# prod5.net
KiCad netlist of a schematic drawn in EAGLE
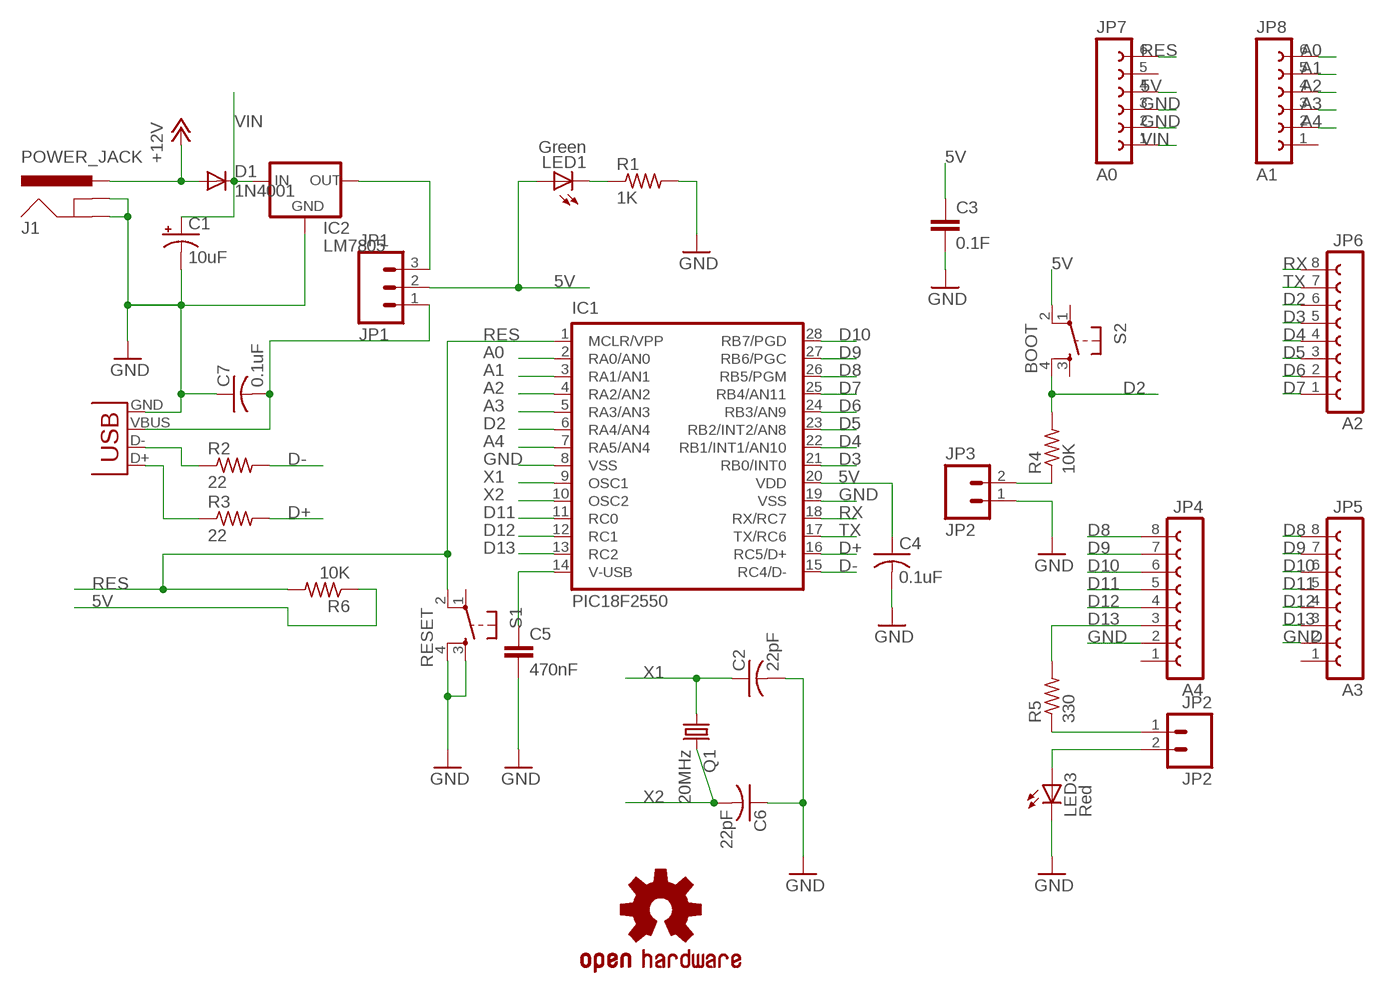
[diagram p0: schematic, sheet 1]

(export (version "E")
  (design (tool "Eeschema 10.0.6"))
  (components
    (comp (ref "C1")
      (value "10uF")
      (footprint "eagle-import:CPOL-RADIAL-10UF-25V")
      (libsource (lib "eagle-import") (part "CAP_POLPTH2"))
    )
    (comp (ref "C2")
      (value "22pF")
      (footprint "eagle-import:C025-025X050")
      (libsource (lib "eagle-import") (part "C-US025-025X050"))
    )
    (comp (ref "C3")
      (value "0.1F")
      (footprint "eagle-import:CAP-PTH-5MM")
      (libsource (lib "eagle-import") (part "CAPPTH1"))
    )
    (comp (ref "C4")
      (value "0.1uF")
      (footprint "eagle-import:C025-025X050")
      (libsource (lib "eagle-import") (part "C-US025-025X050"))
    )
    (comp (ref "C5")
      (value "470nF")
      (footprint "eagle-import:CAP-PTH-5MM")
      (libsource (lib "eagle-import") (part "CAPPTH1"))
    )
    (comp (ref "C6")
      (value "22pF")
      (footprint "eagle-import:C025-025X050")
      (libsource (lib "eagle-import") (part "C-US025-025X050"))
    )
    (comp (ref "C7")
      (value "0.1uF")
      (footprint "eagle-import:C025-025X050")
      (libsource (lib "eagle-import") (part "C-US025-025X050"))
    )
    (comp (ref "D1")
      (value "1N4001")
      (footprint "eagle-import:DIODE-1N4001")
      (libsource (lib "eagle-import") (part "DIODEPTH"))
    )
    (comp (ref "IC1")
      (value "PIC18F2550")
      (footprint "eagle-import:DIL28-3")
      (libsource (lib "eagle-import") (part "PIC18F2550"))
    )
    (comp (ref "IC2")
      (value "LM7805")
      (footprint "eagle-import:78XXL")
      (libsource (lib "eagle-import") (part "V_REG_78XXSIDE"))
    )
    (comp (ref "J1")
      (value "POWER_JACK")
      (footprint "eagle-import:POWER_JACK_PTH")
      (libsource (lib "eagle-import") (part "POWER_JACKPTH"))
    )
    (comp (ref "JP1")
      (value "JP1")
      (footprint "eagle-import:1X03")
      (libsource (lib "eagle-import") (part "M03PTH"))
    )
    (comp (ref "JP2")
      (value "JP2")
      (footprint "eagle-import:1X02")
      (libsource (lib "eagle-import") (part "M02PTH"))
    )
    (comp (ref "JP3")
      (value "JP2")
      (footprint "eagle-import:1X02")
      (libsource (lib "eagle-import") (part "M02PTH"))
    )
    (comp (ref "JP4")
      (value "A4")
      (footprint "eagle-import:FE08")
      (libsource (lib "eagle-import") (part "FE08-1"))
    )
    (comp (ref "JP5")
      (value "A3")
      (footprint "eagle-import:FE08")
      (libsource (lib "eagle-import") (part "FE08-1"))
    )
    (comp (ref "JP6")
      (value "A2")
      (footprint "eagle-import:FE08")
      (libsource (lib "eagle-import") (part "FE08-1"))
    )
    (comp (ref "JP7")
      (value "A0")
      (footprint "eagle-import:FE06")
      (libsource (lib "eagle-import") (part "FE06-1"))
    )
    (comp (ref "JP8")
      (value "A1")
      (footprint "eagle-import:FE06")
      (libsource (lib "eagle-import") (part "FE06-1"))
    )
    (comp (ref "LED1")
      (value "Green")
      (footprint "eagle-import:LED3MM")
      (libsource (lib "eagle-import") (part "LED3MM"))
    )
    (comp (ref "LED3")
      (value "Red")
      (footprint "eagle-import:LED3MM")
      (libsource (lib "eagle-import") (part "LED3MM"))
    )
    (comp (ref "LOGO1")
      (value "OSHW-LOGOM")
      (footprint "eagle-import:OSHW-LOGO-M")
      (libsource (lib "eagle-import") (part "OSHW-LOGOM"))
    )
    (comp (ref "Q1")
      (value "20MHz")
      (footprint "eagle-import:HC49_S")
      (libsource (lib "eagle-import") (part "CRYSTALHC49S"))
    )
    (comp (ref "R1")
      (value "1K")
      (footprint "eagle-import:0204_7")
      (libsource (lib "eagle-import") (part "R-US_0204/7"))
    )
    (comp (ref "R2")
      (value "22")
      (footprint "eagle-import:0207_15")
      (libsource (lib "eagle-import") (part "R-US_0207/15"))
    )
    (comp (ref "R3")
      (value "22")
      (footprint "eagle-import:0207_15")
      (libsource (lib "eagle-import") (part "R-US_0207/15"))
    )
    (comp (ref "R4")
      (value "10K")
      (footprint "eagle-import:0207_15")
      (libsource (lib "eagle-import") (part "R-US_0207/15"))
    )
    (comp (ref "R5")
      (value "330")
      (footprint "eagle-import:0204_7")
      (libsource (lib "eagle-import") (part "R-US_0204/7"))
    )
    (comp (ref "R6")
      (value "10K")
      (footprint "eagle-import:0204_7")
      (libsource (lib "eagle-import") (part "R-US_0204/7"))
    )
    (comp (ref "S1")
      (value "RESET")
      (footprint "eagle-import:TACTILE-PTH")
      (libsource (lib "eagle-import") (part "TAC_SWITCHPTH"))
    )
    (comp (ref "S2")
      (value "BOOT")
      (footprint "eagle-import:TACTILE-PTH")
      (libsource (lib "eagle-import") (part "TAC_SWITCHPTH"))
    )
    (comp (ref "X1")
      (value "USBPTH")
      (footprint "eagle-import:USB-B-PTH")
      (libsource (lib "eagle-import") (part "USBPTH"))
    )
  )
  (nets
    (net (code "1") (name "+12V") (class "Default")
      (node (ref "D1") (pin "A") (pinfunction "A_A") (pintype "passive"))
      (node (ref "J1") (pin "PWR") (pinfunction "PWR_PWR") (pintype "bidirectional"))
    )
    (net (code "2") (name "/5V") (class "Default")
      (node (ref "C3") (pin "1") (pinfunction "1_1") (pintype "passive"))
      (node (ref "C4") (pin "1") (pinfunction "1_1") (pintype "passive"))
      (node (ref "IC1") (pin "20") (pinfunction "VDD_20") (pintype "power_in"))
      (node (ref "JP1") (pin "2") (pinfunction "2_2") (pintype "passive"))
      (node (ref "JP7") (pin "4") (pinfunction "4_4") (pintype "passive"))
      (node (ref "LED1") (pin "A") (pinfunction "A_A") (pintype "passive"))
      (node (ref "R6") (pin "1") (pinfunction "1_1") (pintype "passive"))
      (node (ref "S2") (pin "2") (pinfunction "2_2") (pintype "passive"))
    )
    (net (code "3") (name "/A0") (class "Default")
      (node (ref "IC1") (pin "2") (pinfunction "RA0/AN0_2") (pintype "bidirectional"))
      (node (ref "JP8") (pin "6") (pinfunction "6_6") (pintype "passive"))
    )
    (net (code "4") (name "/A1") (class "Default")
      (node (ref "IC1") (pin "3") (pinfunction "RA1/AN1_3") (pintype "bidirectional"))
      (node (ref "JP8") (pin "5") (pinfunction "5_5") (pintype "passive"))
    )
    (net (code "5") (name "/A2") (class "Default")
      (node (ref "IC1") (pin "4") (pinfunction "RA2/AN2_4") (pintype "bidirectional"))
      (node (ref "JP8") (pin "4") (pinfunction "4_4") (pintype "passive"))
    )
    (net (code "6") (name "/A3") (class "Default")
      (node (ref "IC1") (pin "5") (pinfunction "RA3/AN3_5") (pintype "bidirectional"))
      (node (ref "JP8") (pin "3") (pinfunction "3_3") (pintype "passive"))
    )
    (net (code "7") (name "/A4") (class "Default")
      (node (ref "IC1") (pin "7") (pinfunction "RA5/AN4_7") (pintype "bidirectional"))
      (node (ref "JP8") (pin "2") (pinfunction "2_2") (pintype "passive"))
    )
    (net (code "8") (name "/D+") (class "Default")
      (node (ref "IC1") (pin "16") (pinfunction "RC5/D+_16") (pintype "bidirectional"))
      (node (ref "R3") (pin "2") (pinfunction "2_2") (pintype "passive"))
    )
    (net (code "9") (name "/D-") (class "Default")
      (node (ref "IC1") (pin "15") (pinfunction "RC4/D-_15") (pintype "bidirectional"))
      (node (ref "R2") (pin "2") (pinfunction "2_2") (pintype "passive"))
    )
    (net (code "10") (name "/D2") (class "Default")
      (node (ref "IC1") (pin "6") (pinfunction "RA4/AN4_6") (pintype "bidirectional"))
      (node (ref "JP6") (pin "6") (pinfunction "6_6") (pintype "passive"))
      (node (ref "R4") (pin "2") (pinfunction "2_2") (pintype "passive"))
      (node (ref "S2") (pin "4") (pinfunction "4_4") (pintype "passive"))
    )
    (net (code "11") (name "/D3") (class "Default")
      (node (ref "IC1") (pin "21") (pinfunction "RB0/INT0_21") (pintype "bidirectional"))
      (node (ref "JP6") (pin "5") (pinfunction "5_5") (pintype "passive"))
    )
    (net (code "12") (name "/D4") (class "Default")
      (node (ref "IC1") (pin "22") (pinfunction "RB1/INT1/AN10_22") (pintype "bidirectional"))
      (node (ref "JP6") (pin "4") (pinfunction "4_4") (pintype "passive"))
    )
    (net (code "13") (name "/D5") (class "Default")
      (node (ref "IC1") (pin "23") (pinfunction "RB2/INT2/AN8_23") (pintype "bidirectional"))
      (node (ref "JP6") (pin "3") (pinfunction "3_3") (pintype "passive"))
    )
    (net (code "14") (name "/D6") (class "Default")
      (node (ref "IC1") (pin "24") (pinfunction "RB3/AN9_24") (pintype "bidirectional"))
      (node (ref "JP6") (pin "2") (pinfunction "2_2") (pintype "passive"))
    )
    (net (code "15") (name "/D7") (class "Default")
      (node (ref "IC1") (pin "25") (pinfunction "RB4/AN11_25") (pintype "bidirectional"))
      (node (ref "JP6") (pin "1") (pinfunction "1_1") (pintype "passive"))
    )
    (net (code "16") (name "/D8") (class "Default")
      (node (ref "IC1") (pin "26") (pinfunction "RB5/PGM_26") (pintype "bidirectional"))
      (node (ref "JP4") (pin "8") (pinfunction "8_8") (pintype "passive"))
      (node (ref "JP5") (pin "8") (pinfunction "8_8") (pintype "passive"))
    )
    (net (code "17") (name "/D9") (class "Default")
      (node (ref "IC1") (pin "27") (pinfunction "RB6/PGC_27") (pintype "bidirectional"))
      (node (ref "JP4") (pin "7") (pinfunction "7_7") (pintype "passive"))
      (node (ref "JP5") (pin "7") (pinfunction "7_7") (pintype "passive"))
    )
    (net (code "18") (name "/D10") (class "Default")
      (node (ref "IC1") (pin "28") (pinfunction "RB7/PGD_28") (pintype "bidirectional"))
      (node (ref "JP4") (pin "6") (pinfunction "6_6") (pintype "passive"))
      (node (ref "JP5") (pin "6") (pinfunction "6_6") (pintype "passive"))
    )
    (net (code "19") (name "/D11") (class "Default")
      (node (ref "IC1") (pin "11") (pinfunction "RC0_11") (pintype "bidirectional"))
      (node (ref "JP4") (pin "5") (pinfunction "5_5") (pintype "passive"))
      (node (ref "JP5") (pin "5") (pinfunction "5_5") (pintype "passive"))
    )
    (net (code "20") (name "/D12") (class "Default")
      (node (ref "IC1") (pin "12") (pinfunction "RC1_12") (pintype "bidirectional"))
      (node (ref "JP4") (pin "4") (pinfunction "4_4") (pintype "passive"))
      (node (ref "JP5") (pin "4") (pinfunction "4_4") (pintype "passive"))
    )
    (net (code "21") (name "/D13") (class "Default")
      (node (ref "IC1") (pin "13") (pinfunction "RC2_13") (pintype "bidirectional"))
      (node (ref "JP4") (pin "3") (pinfunction "3_3") (pintype "passive"))
      (node (ref "JP5") (pin "3") (pinfunction "3_3") (pintype "passive"))
      (node (ref "R5") (pin "2") (pinfunction "2_2") (pintype "passive"))
    )
    (net (code "22") (name "/RES") (class "Default")
      (node (ref "IC1") (pin "1") (pinfunction "MCLR/VPP_1") (pintype "bidirectional"))
      (node (ref "JP7") (pin "6") (pinfunction "6_6") (pintype "passive"))
      (node (ref "R6") (pin "2") (pinfunction "2_2") (pintype "passive"))
      (node (ref "S1") (pin "2") (pinfunction "2_2") (pintype "passive"))
    )
    (net (code "23") (name "/RX") (class "Default")
      (node (ref "IC1") (pin "18") (pinfunction "RX/RC7_18") (pintype "input"))
      (node (ref "JP6") (pin "8") (pinfunction "8_8") (pintype "passive"))
    )
    (net (code "24") (name "/TX") (class "Default")
      (node (ref "IC1") (pin "17") (pinfunction "TX/RC6_17") (pintype "bidirectional"))
      (node (ref "JP6") (pin "7") (pinfunction "7_7") (pintype "passive"))
    )
    (net (code "25") (name "/VIN") (class "Default")
      (node (ref "C1") (pin "1") (pinfunction "+_1") (pintype "passive"))
      (node (ref "D1") (pin "C") (pinfunction "C_C") (pintype "passive"))
      (node (ref "IC2") (pin "IN") (pinfunction "IN_IN") (pintype "input"))
      (node (ref "JP7") (pin "1") (pinfunction "1_1") (pintype "passive"))
    )
    (net (code "26") (name "/X1") (class "Default")
      (node (ref "C2") (pin "1") (pinfunction "1_1") (pintype "passive"))
      (node (ref "IC1") (pin "9") (pinfunction "OSC1_9") (pintype "bidirectional"))
      (node (ref "Q1") (pin "1") (pinfunction "1_1") (pintype "passive"))
    )
    (net (code "27") (name "/X2") (class "Default")
      (node (ref "C6") (pin "2") (pinfunction "2_2") (pintype "passive"))
      (node (ref "IC1") (pin "10") (pinfunction "OSC2_10") (pintype "bidirectional"))
      (node (ref "Q1") (pin "2") (pinfunction "2_2") (pintype "passive"))
    )
    (net (code "28") (name "GND") (class "Default")
      (node (ref "C1") (pin "2") (pinfunction "-_2") (pintype "passive"))
      (node (ref "C2") (pin "2") (pinfunction "2_2") (pintype "passive"))
      (node (ref "C3") (pin "2") (pinfunction "2_2") (pintype "passive"))
      (node (ref "C4") (pin "2") (pinfunction "2_2") (pintype "passive"))
      (node (ref "C5") (pin "2") (pinfunction "2_2") (pintype "passive"))
      (node (ref "C6") (pin "1") (pinfunction "1_1") (pintype "passive"))
      (node (ref "C7") (pin "1") (pinfunction "1_1") (pintype "passive"))
      (node (ref "IC1") (pin "19") (pinfunction "VSS_19") (pintype "power_in"))
      (node (ref "IC1") (pin "8") (pinfunction "VSS_8") (pintype "power_in"))
      (node (ref "IC2") (pin "GND") (pinfunction "GND_GND") (pintype "input"))
      (node (ref "J1") (pin "GND") (pinfunction "GND_GND") (pintype "bidirectional"))
      (node (ref "J1") (pin "GNDBREAK") (pinfunction "GNDBREAK_GNDBREAK") (pintype "bidirectional"))
      (node (ref "JP3") (pin "1") (pinfunction "1_1") (pintype "passive"))
      (node (ref "JP4") (pin "2") (pinfunction "2_2") (pintype "passive"))
      (node (ref "JP5") (pin "2") (pinfunction "2_2") (pintype "passive"))
      (node (ref "JP7") (pin "2") (pinfunction "2_2") (pintype "passive"))
      (node (ref "JP7") (pin "3") (pinfunction "3_3") (pintype "passive"))
      (node (ref "LED3") (pin "K") (pinfunction "C_K") (pintype "passive"))
      (node (ref "R1") (pin "2") (pinfunction "2_2") (pintype "passive"))
      (node (ref "S1") (pin "3") (pinfunction "3_3") (pintype "passive"))
      (node (ref "S1") (pin "4") (pinfunction "4_4") (pintype "passive"))
      (node (ref "X1") (pin "GND") (pinfunction "GND_GND") (pintype "bidirectional"))
    )
    (net (code "29") (name "Net-(C7-Pad2)") (class "Default")
      (node (ref "C7") (pin "2") (pinfunction "2_2") (pintype "passive"))
      (node (ref "JP1") (pin "1") (pinfunction "1_1") (pintype "passive"))
      (node (ref "X1") (pin "VBUS") (pinfunction "VBUS_VBUS") (pintype "bidirectional"))
    )
    (net (code "30") (name "Net-(IC1-V-USB)") (class "Default")
      (node (ref "C5") (pin "1") (pinfunction "1_1") (pintype "passive"))
      (node (ref "IC1") (pin "14") (pinfunction "V-USB_14") (pintype "bidirectional"))
    )
    (net (code "31") (name "Net-(IC2-PadOUT)") (class "Default")
      (node (ref "IC2") (pin "OUT") (pinfunction "OUT_OUT") (pintype "output"))
      (node (ref "JP1") (pin "3") (pinfunction "3_3") (pintype "passive"))
    )
    (net (code "32") (name "Net-(JP2-Pad1)") (class "Default")
      (node (ref "JP2") (pin "1") (pinfunction "1_1") (pintype "passive"))
      (node (ref "R5") (pin "1") (pinfunction "1_1") (pintype "passive"))
    )
    (net (code "33") (name "Net-(JP2-Pad2)") (class "Default")
      (node (ref "JP2") (pin "2") (pinfunction "2_2") (pintype "passive"))
      (node (ref "LED3") (pin "A") (pinfunction "A_A") (pintype "passive"))
    )
    (net (code "34") (name "Net-(JP3-Pad2)") (class "Default")
      (node (ref "JP3") (pin "2") (pinfunction "2_2") (pintype "passive"))
      (node (ref "R4") (pin "1") (pinfunction "1_1") (pintype "passive"))
    )
    (net (code "35") (name "Net-(LED1-C)") (class "Default")
      (node (ref "LED1") (pin "K") (pinfunction "C_K") (pintype "passive"))
      (node (ref "R1") (pin "1") (pinfunction "1_1") (pintype "passive"))
    )
    (net (code "36") (name "Net-(R2-Pad1)") (class "Default")
      (node (ref "R2") (pin "1") (pinfunction "1_1") (pintype "passive"))
      (node (ref "X1") (pin "D-") (pinfunction "D-_D-") (pintype "bidirectional"))
    )
    (net (code "37") (name "Net-(R3-Pad1)") (class "Default")
      (node (ref "R3") (pin "1") (pinfunction "1_1") (pintype "passive"))
      (node (ref "X1") (pin "D+") (pinfunction "D+_D+") (pintype "bidirectional"))
    )
    (net (code "38") (name "unconnected-(JP4-Pad1)") (class "Default")
      (node (ref "JP4") (pin "1") (pinfunction "1_1") (pintype "passive"))
    )
    (net (code "39") (name "unconnected-(JP5-Pad1)") (class "Default")
      (node (ref "JP5") (pin "1") (pinfunction "1_1") (pintype "passive"))
    )
    (net (code "40") (name "unconnected-(JP7-Pad5)") (class "Default")
      (node (ref "JP7") (pin "5") (pinfunction "5_5") (pintype "passive"))
    )
    (net (code "41") (name "unconnected-(JP8-Pad1)") (class "Default")
      (node (ref "JP8") (pin "1") (pinfunction "1_1") (pintype "passive"))
    )
    (net (code "42") (name "unconnected-(S1-Pad1)") (class "Default")
      (node (ref "S1") (pin "1") (pinfunction "1_1") (pintype "passive"))
    )
    (net (code "43") (name "unconnected-(S2-Pad1)") (class "Default")
      (node (ref "S2") (pin "1") (pinfunction "1_1") (pintype "passive"))
    )
    (net (code "44") (name "unconnected-(S2-Pad3)") (class "Default")
      (node (ref "S2") (pin "3") (pinfunction "3_3") (pintype "passive"))
    )
  )
)
